# conn_board.net
KiCad netlist of a schematic drawn in EAGLE
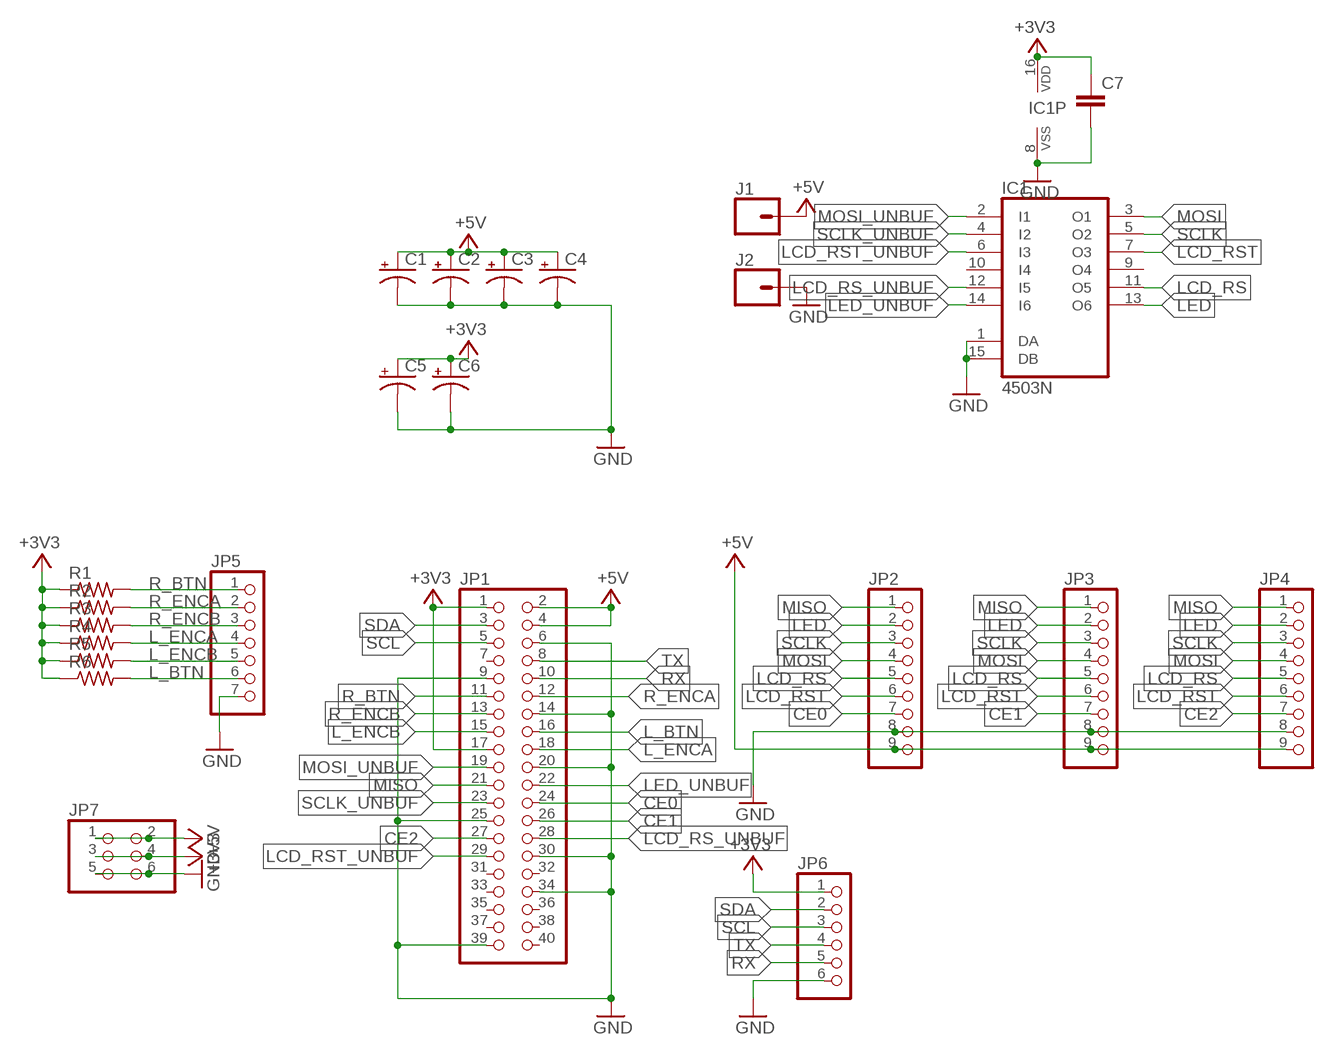
[diagram p0: schematic, sheet 1]

(export (version "E")
  (design (tool "Eeschema 10.0.6"))
  (components
    (comp (ref "C1")
      (value "CPOL-USSANYO_F13")
      (footprint "eagle-import:SANYO-OSCON_F13")
      (libsource (lib "eagle-import") (part "CPOL-USSANYO_F13"))
    )
    (comp (ref "C2")
      (value "CPOL-USSANYO_F13")
      (footprint "eagle-import:SANYO-OSCON_F13")
      (libsource (lib "eagle-import") (part "CPOL-USSANYO_F13"))
    )
    (comp (ref "C3")
      (value "CPOL-USSANYO_F13")
      (footprint "eagle-import:SANYO-OSCON_F13")
      (libsource (lib "eagle-import") (part "CPOL-USSANYO_F13"))
    )
    (comp (ref "C4")
      (value "CPOL-USSANYO_F13")
      (footprint "eagle-import:SANYO-OSCON_F13")
      (libsource (lib "eagle-import") (part "CPOL-USSANYO_F13"))
    )
    (comp (ref "C5")
      (value "CPOL-USSANYO_F13")
      (footprint "eagle-import:SANYO-OSCON_F13")
      (libsource (lib "eagle-import") (part "CPOL-USSANYO_F13"))
    )
    (comp (ref "C6")
      (value "CPOL-USSANYO_F13")
      (footprint "eagle-import:SANYO-OSCON_F13")
      (libsource (lib "eagle-import") (part "CPOL-USSANYO_F13"))
    )
    (comp (ref "C7")
      (value "C-EU050-055X075")
      (footprint "eagle-import:C050-055X075")
      (libsource (lib "eagle-import") (part "C-EU050-055X075"))
    )
    (comp (ref "IC1")
      (value "4503N")
      (footprint "eagle-import:DIL16")
      (libsource (lib "eagle-import") (part "4503N"))
    )
    (comp (ref "J1")
      (value "CONN_01PTH_LONGPAD")
      (footprint "eagle-import:1X01_LONGPAD")
      (libsource (lib "eagle-import") (part "CONN_01PTH_LONGPAD"))
    )
    (comp (ref "J2")
      (value "CONN_01PTH_LONGPAD")
      (footprint "eagle-import:1X01_LONGPAD")
      (libsource (lib "eagle-import") (part "CONN_01PTH_LONGPAD"))
    )
    (comp (ref "JP1")
      (value "PINHD-2X20")
      (footprint "eagle-import:2X20")
      (libsource (lib "eagle-import") (part "PINHD-2X20"))
    )
    (comp (ref "JP2")
      (value "PINHD-1X9")
      (footprint "eagle-import:1X09")
      (libsource (lib "eagle-import") (part "PINHD-1X9"))
    )
    (comp (ref "JP3")
      (value "PINHD-1X9")
      (footprint "eagle-import:1X09")
      (libsource (lib "eagle-import") (part "PINHD-1X9"))
    )
    (comp (ref "JP4")
      (value "PINHD-1X9")
      (footprint "eagle-import:1X09")
      (libsource (lib "eagle-import") (part "PINHD-1X9"))
    )
    (comp (ref "JP5")
      (value "PINHD-1X7")
      (footprint "eagle-import:1X07")
      (libsource (lib "eagle-import") (part "PINHD-1X7"))
    )
    (comp (ref "JP6")
      (value "PINHD-1X6")
      (footprint "eagle-import:1X06")
      (libsource (lib "eagle-import") (part "PINHD-1X6"))
    )
    (comp (ref "JP7")
      (value "PINHD-2X3")
      (footprint "eagle-import:2X03")
      (libsource (lib "eagle-import") (part "PINHD-2X3"))
    )
    (comp (ref "R1")
      (value "R-US_0207/10")
      (footprint "eagle-import:0207_10")
      (libsource (lib "eagle-import") (part "R-US_0207/10"))
    )
    (comp (ref "R2")
      (value "R-US_0207/10")
      (footprint "eagle-import:0207_10")
      (libsource (lib "eagle-import") (part "R-US_0207/10"))
    )
    (comp (ref "R3")
      (value "R-US_0207/10")
      (footprint "eagle-import:0207_10")
      (libsource (lib "eagle-import") (part "R-US_0207/10"))
    )
    (comp (ref "R4")
      (value "R-US_0207/10")
      (footprint "eagle-import:0207_10")
      (libsource (lib "eagle-import") (part "R-US_0207/10"))
    )
    (comp (ref "R5")
      (value "R-US_0207/10")
      (footprint "eagle-import:0207_10")
      (libsource (lib "eagle-import") (part "R-US_0207/10"))
    )
    (comp (ref "R6")
      (value "R-US_0207/10")
      (footprint "eagle-import:0207_10")
      (libsource (lib "eagle-import") (part "R-US_0207/10"))
    )
  )
  (nets
    (net (code "1") (name "+3V3") (class "Default")
      (node (ref "C5") (pin "+") (pinfunction "+_+") (pintype "passive"))
      (node (ref "C6") (pin "+") (pinfunction "+_+") (pintype "passive"))
      (node (ref "C7") (pin "1") (pinfunction "1_1") (pintype "passive"))
      (node (ref "IC1") (pin "16") (pinfunction "VDD_16") (pintype "power_in"))
      (node (ref "JP1") (pin "1") (pinfunction "1_1") (pintype "passive"))
      (node (ref "JP1") (pin "17") (pinfunction "17_17") (pintype "passive"))
      (node (ref "JP6") (pin "1") (pinfunction "1_1") (pintype "passive"))
      (node (ref "JP7") (pin "3") (pinfunction "3_3") (pintype "passive"))
      (node (ref "JP7") (pin "4") (pinfunction "4_4") (pintype "passive"))
      (node (ref "R1") (pin "1") (pinfunction "1_1") (pintype "passive"))
      (node (ref "R2") (pin "1") (pinfunction "1_1") (pintype "passive"))
      (node (ref "R3") (pin "1") (pinfunction "1_1") (pintype "passive"))
      (node (ref "R4") (pin "1") (pinfunction "1_1") (pintype "passive"))
      (node (ref "R5") (pin "1") (pinfunction "1_1") (pintype "passive"))
      (node (ref "R6") (pin "1") (pinfunction "1_1") (pintype "passive"))
    )
    (net (code "2") (name "+5V") (class "Default")
      (node (ref "C1") (pin "+") (pinfunction "+_+") (pintype "passive"))
      (node (ref "C2") (pin "+") (pinfunction "+_+") (pintype "passive"))
      (node (ref "C3") (pin "+") (pinfunction "+_+") (pintype "passive"))
      (node (ref "C4") (pin "+") (pinfunction "+_+") (pintype "passive"))
      (node (ref "J1") (pin "1") (pinfunction "1_1") (pintype "passive"))
      (node (ref "JP1") (pin "2") (pinfunction "2_2") (pintype "passive"))
      (node (ref "JP1") (pin "4") (pinfunction "4_4") (pintype "passive"))
      (node (ref "JP2") (pin "9") (pinfunction "9_9") (pintype "passive"))
      (node (ref "JP3") (pin "9") (pinfunction "9_9") (pintype "passive"))
      (node (ref "JP4") (pin "9") (pinfunction "9_9") (pintype "passive"))
      (node (ref "JP7") (pin "1") (pinfunction "1_1") (pintype "passive"))
      (node (ref "JP7") (pin "2") (pinfunction "2_2") (pintype "passive"))
    )
    (net (code "3") (name "CE0") (class "Default")
      (node (ref "JP1") (pin "24") (pinfunction "24_24") (pintype "passive"))
      (node (ref "JP2") (pin "7") (pinfunction "7_7") (pintype "passive"))
    )
    (net (code "4") (name "CE1") (class "Default")
      (node (ref "JP1") (pin "26") (pinfunction "26_26") (pintype "passive"))
      (node (ref "JP3") (pin "7") (pinfunction "7_7") (pintype "passive"))
    )
    (net (code "5") (name "CE2") (class "Default")
      (node (ref "JP1") (pin "27") (pinfunction "27_27") (pintype "passive"))
      (node (ref "JP4") (pin "7") (pinfunction "7_7") (pintype "passive"))
    )
    (net (code "6") (name "GND") (class "Default")
      (node (ref "C1") (pin "-") (pinfunction "-_-") (pintype "passive"))
      (node (ref "C2") (pin "-") (pinfunction "-_-") (pintype "passive"))
      (node (ref "C3") (pin "-") (pinfunction "-_-") (pintype "passive"))
      (node (ref "C4") (pin "-") (pinfunction "-_-") (pintype "passive"))
      (node (ref "C5") (pin "-") (pinfunction "-_-") (pintype "passive"))
      (node (ref "C6") (pin "-") (pinfunction "-_-") (pintype "passive"))
      (node (ref "C7") (pin "2") (pinfunction "2_2") (pintype "passive"))
      (node (ref "IC1") (pin "1") (pinfunction "DA_1") (pintype "input"))
      (node (ref "IC1") (pin "15") (pinfunction "DB_15") (pintype "input"))
      (node (ref "IC1") (pin "8") (pinfunction "VSS_8") (pintype "power_in"))
      (node (ref "J2") (pin "1") (pinfunction "1_1") (pintype "passive"))
      (node (ref "JP1") (pin "14") (pinfunction "14_14") (pintype "passive"))
      (node (ref "JP1") (pin "20") (pinfunction "20_20") (pintype "passive"))
      (node (ref "JP1") (pin "25") (pinfunction "25_25") (pintype "passive"))
      (node (ref "JP1") (pin "30") (pinfunction "30_30") (pintype "passive"))
      (node (ref "JP1") (pin "34") (pinfunction "34_34") (pintype "passive"))
      (node (ref "JP1") (pin "39") (pinfunction "39_39") (pintype "passive"))
      (node (ref "JP1") (pin "6") (pinfunction "6_6") (pintype "passive"))
      (node (ref "JP1") (pin "9") (pinfunction "9_9") (pintype "passive"))
      (node (ref "JP2") (pin "8") (pinfunction "8_8") (pintype "passive"))
      (node (ref "JP3") (pin "8") (pinfunction "8_8") (pintype "passive"))
      (node (ref "JP4") (pin "8") (pinfunction "8_8") (pintype "passive"))
      (node (ref "JP5") (pin "7") (pinfunction "7_7") (pintype "passive"))
      (node (ref "JP6") (pin "6") (pinfunction "6_6") (pintype "passive"))
      (node (ref "JP7") (pin "5") (pinfunction "5_5") (pintype "passive"))
      (node (ref "JP7") (pin "6") (pinfunction "6_6") (pintype "passive"))
    )
    (net (code "7") (name "LCD_RS") (class "Default")
      (node (ref "IC1") (pin "11") (pinfunction "O5_11") (pintype "output"))
      (node (ref "JP2") (pin "5") (pinfunction "5_5") (pintype "passive"))
      (node (ref "JP3") (pin "5") (pinfunction "5_5") (pintype "passive"))
      (node (ref "JP4") (pin "5") (pinfunction "5_5") (pintype "passive"))
    )
    (net (code "8") (name "LCD_RST") (class "Default")
      (node (ref "IC1") (pin "7") (pinfunction "O3_7") (pintype "output"))
      (node (ref "JP2") (pin "6") (pinfunction "6_6") (pintype "passive"))
      (node (ref "JP3") (pin "6") (pinfunction "6_6") (pintype "passive"))
      (node (ref "JP4") (pin "6") (pinfunction "6_6") (pintype "passive"))
    )
    (net (code "9") (name "LCD_RST_UNBUF") (class "Default")
      (node (ref "IC1") (pin "6") (pinfunction "I3_6") (pintype "input"))
      (node (ref "JP1") (pin "29") (pinfunction "29_29") (pintype "passive"))
    )
    (net (code "10") (name "LCD_RS_UNBUF") (class "Default")
      (node (ref "IC1") (pin "12") (pinfunction "I5_12") (pintype "input"))
      (node (ref "JP1") (pin "28") (pinfunction "28_28") (pintype "passive"))
    )
    (net (code "11") (name "LED") (class "Default")
      (node (ref "IC1") (pin "13") (pinfunction "O6_13") (pintype "output"))
      (node (ref "JP2") (pin "2") (pinfunction "2_2") (pintype "passive"))
      (node (ref "JP3") (pin "2") (pinfunction "2_2") (pintype "passive"))
      (node (ref "JP4") (pin "2") (pinfunction "2_2") (pintype "passive"))
    )
    (net (code "12") (name "LED_UNBUF") (class "Default")
      (node (ref "IC1") (pin "14") (pinfunction "I6_14") (pintype "input"))
      (node (ref "JP1") (pin "22") (pinfunction "22_22") (pintype "passive"))
    )
    (net (code "13") (name "L_BTN") (class "Default")
      (node (ref "JP1") (pin "16") (pinfunction "16_16") (pintype "passive"))
      (node (ref "JP5") (pin "6") (pinfunction "6_6") (pintype "passive"))
      (node (ref "R6") (pin "2") (pinfunction "2_2") (pintype "passive"))
    )
    (net (code "14") (name "L_ENCA") (class "Default")
      (node (ref "JP1") (pin "18") (pinfunction "18_18") (pintype "passive"))
      (node (ref "JP5") (pin "4") (pinfunction "4_4") (pintype "passive"))
      (node (ref "R4") (pin "2") (pinfunction "2_2") (pintype "passive"))
    )
    (net (code "15") (name "L_ENCB") (class "Default")
      (node (ref "JP1") (pin "15") (pinfunction "15_15") (pintype "passive"))
      (node (ref "JP5") (pin "5") (pinfunction "5_5") (pintype "passive"))
      (node (ref "R5") (pin "2") (pinfunction "2_2") (pintype "passive"))
    )
    (net (code "16") (name "MISO") (class "Default")
      (node (ref "JP1") (pin "21") (pinfunction "21_21") (pintype "passive"))
      (node (ref "JP2") (pin "1") (pinfunction "1_1") (pintype "passive"))
      (node (ref "JP3") (pin "1") (pinfunction "1_1") (pintype "passive"))
      (node (ref "JP4") (pin "1") (pinfunction "1_1") (pintype "passive"))
    )
    (net (code "17") (name "MOSI") (class "Default")
      (node (ref "IC1") (pin "3") (pinfunction "O1_3") (pintype "output"))
      (node (ref "JP2") (pin "4") (pinfunction "4_4") (pintype "passive"))
      (node (ref "JP3") (pin "4") (pinfunction "4_4") (pintype "passive"))
      (node (ref "JP4") (pin "4") (pinfunction "4_4") (pintype "passive"))
    )
    (net (code "18") (name "MOSI_UNBUF") (class "Default")
      (node (ref "IC1") (pin "2") (pinfunction "I1_2") (pintype "input"))
      (node (ref "JP1") (pin "19") (pinfunction "19_19") (pintype "passive"))
    )
    (net (code "19") (name "RX") (class "Default")
      (node (ref "JP1") (pin "10") (pinfunction "10_10") (pintype "passive"))
      (node (ref "JP6") (pin "5") (pinfunction "5_5") (pintype "passive"))
    )
    (net (code "20") (name "R_BTN") (class "Default")
      (node (ref "JP1") (pin "11") (pinfunction "11_11") (pintype "passive"))
      (node (ref "JP5") (pin "1") (pinfunction "1_1") (pintype "passive"))
      (node (ref "R1") (pin "2") (pinfunction "2_2") (pintype "passive"))
    )
    (net (code "21") (name "R_ENCA") (class "Default")
      (node (ref "JP1") (pin "12") (pinfunction "12_12") (pintype "passive"))
      (node (ref "JP5") (pin "2") (pinfunction "2_2") (pintype "passive"))
      (node (ref "R2") (pin "2") (pinfunction "2_2") (pintype "passive"))
    )
    (net (code "22") (name "R_ENCB") (class "Default")
      (node (ref "JP1") (pin "13") (pinfunction "13_13") (pintype "passive"))
      (node (ref "JP5") (pin "3") (pinfunction "3_3") (pintype "passive"))
      (node (ref "R3") (pin "2") (pinfunction "2_2") (pintype "passive"))
    )
    (net (code "23") (name "SCL") (class "Default")
      (node (ref "JP1") (pin "5") (pinfunction "5_5") (pintype "passive"))
      (node (ref "JP6") (pin "3") (pinfunction "3_3") (pintype "passive"))
    )
    (net (code "24") (name "SCLK") (class "Default")
      (node (ref "IC1") (pin "5") (pinfunction "O2_5") (pintype "output"))
      (node (ref "JP2") (pin "3") (pinfunction "3_3") (pintype "passive"))
      (node (ref "JP3") (pin "3") (pinfunction "3_3") (pintype "passive"))
      (node (ref "JP4") (pin "3") (pinfunction "3_3") (pintype "passive"))
    )
    (net (code "25") (name "SCLK_UNBUF") (class "Default")
      (node (ref "IC1") (pin "4") (pinfunction "I2_4") (pintype "input"))
      (node (ref "JP1") (pin "23") (pinfunction "23_23") (pintype "passive"))
    )
    (net (code "26") (name "SDA") (class "Default")
      (node (ref "JP1") (pin "3") (pinfunction "3_3") (pintype "passive"))
      (node (ref "JP6") (pin "2") (pinfunction "2_2") (pintype "passive"))
    )
    (net (code "27") (name "TX") (class "Default")
      (node (ref "JP1") (pin "8") (pinfunction "8_8") (pintype "passive"))
      (node (ref "JP6") (pin "4") (pinfunction "4_4") (pintype "passive"))
    )
    (net (code "28") (name "unconnected-(IC1A-I4-Pad10)") (class "Default")
      (node (ref "IC1") (pin "10") (pinfunction "I4_10") (pintype "input"))
    )
    (net (code "29") (name "unconnected-(IC1A-O4-Pad9)") (class "Default")
      (node (ref "IC1") (pin "9") (pinfunction "O4_9") (pintype "output"))
    )
    (net (code "30") (name "unconnected-(JP1-Pad7)") (class "Default")
      (node (ref "JP1") (pin "7") (pinfunction "7_7") (pintype "passive"))
    )
    (net (code "31") (name "unconnected-(JP1-Pad31)") (class "Default")
      (node (ref "JP1") (pin "31") (pinfunction "31_31") (pintype "passive"))
    )
    (net (code "32") (name "unconnected-(JP1-Pad32)") (class "Default")
      (node (ref "JP1") (pin "32") (pinfunction "32_32") (pintype "passive"))
    )
    (net (code "33") (name "unconnected-(JP1-Pad33)") (class "Default")
      (node (ref "JP1") (pin "33") (pinfunction "33_33") (pintype "passive"))
    )
    (net (code "34") (name "unconnected-(JP1-Pad35)") (class "Default")
      (node (ref "JP1") (pin "35") (pinfunction "35_35") (pintype "passive"))
    )
    (net (code "35") (name "unconnected-(JP1-Pad36)") (class "Default")
      (node (ref "JP1") (pin "36") (pinfunction "36_36") (pintype "passive"))
    )
    (net (code "36") (name "unconnected-(JP1-Pad37)") (class "Default")
      (node (ref "JP1") (pin "37") (pinfunction "37_37") (pintype "passive"))
    )
    (net (code "37") (name "unconnected-(JP1-Pad38)") (class "Default")
      (node (ref "JP1") (pin "38") (pinfunction "38_38") (pintype "passive"))
    )
    (net (code "38") (name "unconnected-(JP1-Pad40)") (class "Default")
      (node (ref "JP1") (pin "40") (pinfunction "40_40") (pintype "passive"))
    )
  )
)
